# Potenta_connections.net
KiCad netlist of a schematic drawn in Altium Designer
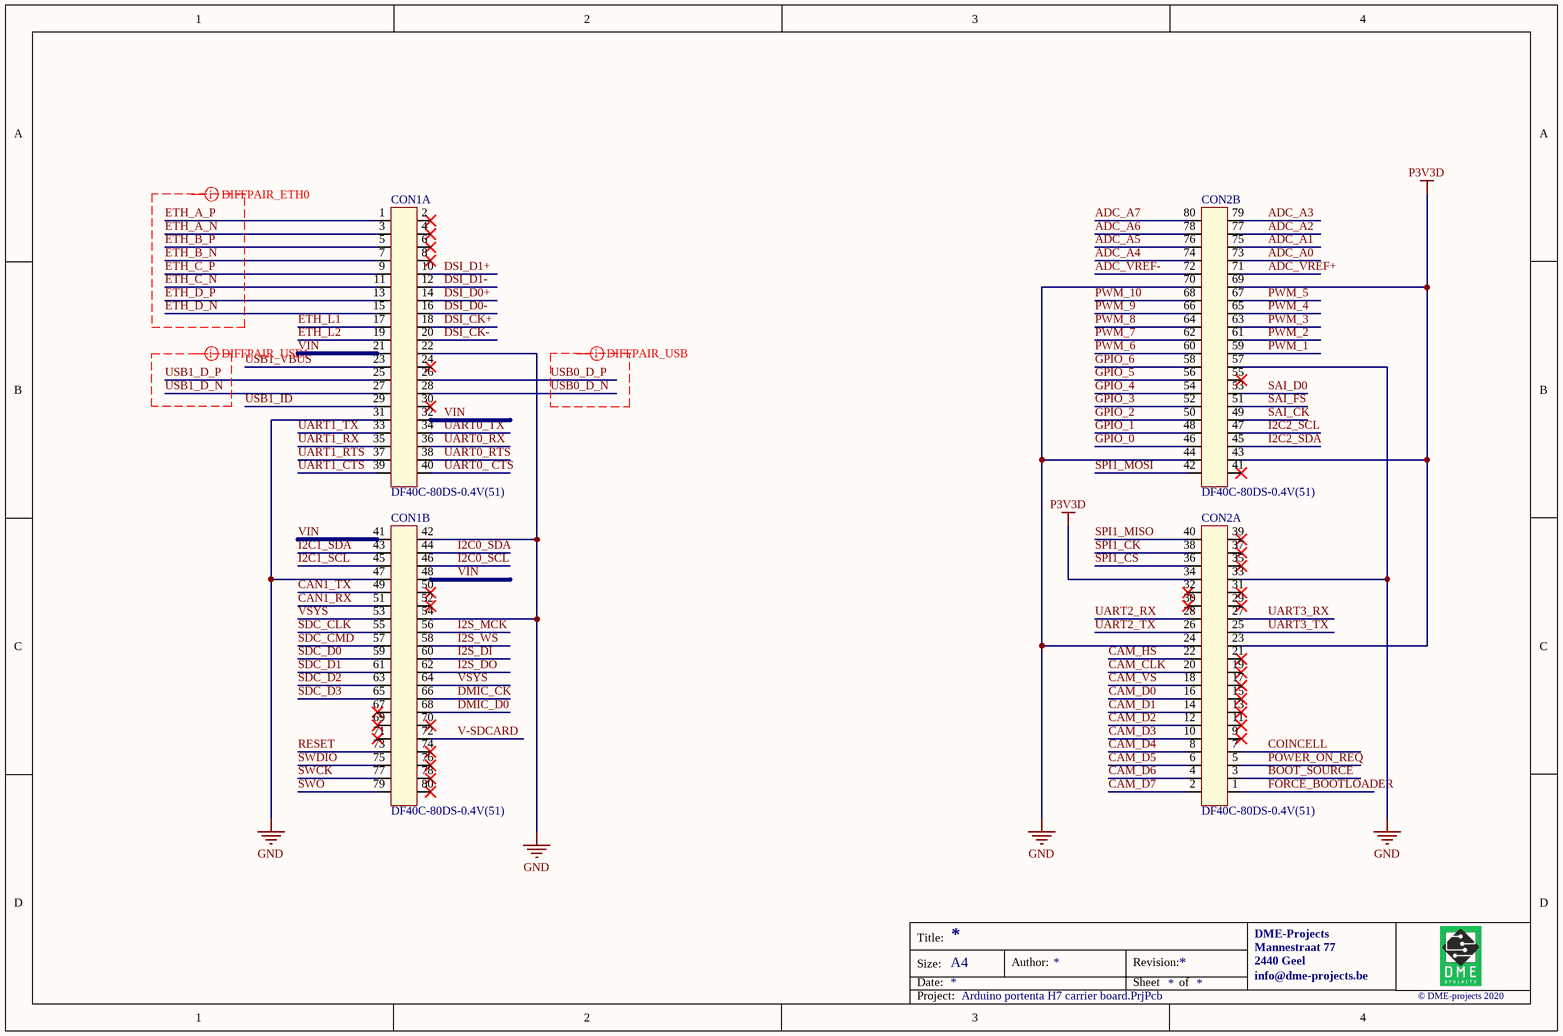
[diagram p0: Potenta connections.SchDoc]

(export (version "E")
  (design (tool "Eeschema 10.0.6"))
  (components
    (comp (ref "CON1")
      (value "DF40C-80DS-0.4V(51)")
      (footprint "DF40C-80DS-0.4V(51)-Footprint-1")
      (description "DF40 Series 80 Positions 0.4 mm Pitch Dual Row SMT Receptacle Connector")
      (libsource (lib "") (part "DF40C-80DS-0.4V(51)_1"))
    )
    (comp (ref "CON2")
      (value "DF40C-80DS-0.4V(51)")
      (footprint "DF40C-80DS-0.4V(51)-Footprint-1")
      (description "DF40 Series 80 Positions 0.4 mm Pitch Dual Row SMT Receptacle Connector")
      (libsource (lib "MIRION Technologies (CANBERRA Olen) NV") (part "DF40C-80DS-0.4V(51)"))
    )
  )
  (nets
    (net (code "1") (name "/ADC_A0") (class "Default")
      (node (ref "CON2") (pin "73") (pinfunction "73_73") (pintype "passive"))
    )
    (net (code "2") (name "/ADC_A1") (class "Default")
      (node (ref "CON2") (pin "75") (pinfunction "75_75") (pintype "passive"))
    )
    (net (code "3") (name "/ADC_A2") (class "Default")
      (node (ref "CON2") (pin "77") (pinfunction "77_77") (pintype "passive"))
    )
    (net (code "4") (name "/ADC_A3") (class "Default")
      (node (ref "CON2") (pin "79") (pinfunction "79_79") (pintype "passive"))
    )
    (net (code "5") (name "/ADC_A4") (class "Default")
      (node (ref "CON2") (pin "74") (pinfunction "74_74") (pintype "passive"))
    )
    (net (code "6") (name "/ADC_A5") (class "Default")
      (node (ref "CON2") (pin "76") (pinfunction "76_76") (pintype "passive"))
    )
    (net (code "7") (name "/ADC_A6") (class "Default")
      (node (ref "CON2") (pin "78") (pinfunction "78_78") (pintype "passive"))
    )
    (net (code "8") (name "/ADC_A7") (class "Default")
      (node (ref "CON2") (pin "80") (pinfunction "80_80") (pintype "passive"))
    )
    (net (code "9") (name "/ADC_VREF+") (class "Default")
      (node (ref "CON2") (pin "71") (pinfunction "71_71") (pintype "passive"))
    )
    (net (code "10") (name "/ADC_VREF-") (class "Default")
      (node (ref "CON2") (pin "72") (pinfunction "72_72") (pintype "passive"))
    )
    (net (code "11") (name "/BOOT_SOURCE") (class "Default")
      (node (ref "CON2") (pin "3") (pinfunction "3_3") (pintype "passive"))
    )
    (net (code "12") (name "/CAM_CLK") (class "Default")
      (node (ref "CON2") (pin "20") (pinfunction "20_20") (pintype "passive"))
    )
    (net (code "13") (name "/CAM_D0") (class "Default")
      (node (ref "CON2") (pin "16") (pinfunction "16_16") (pintype "passive"))
    )
    (net (code "14") (name "/CAM_D1") (class "Default")
      (node (ref "CON2") (pin "14") (pinfunction "14_14") (pintype "passive"))
    )
    (net (code "15") (name "/CAM_D2") (class "Default")
      (node (ref "CON2") (pin "12") (pinfunction "12_12") (pintype "passive"))
    )
    (net (code "16") (name "/CAM_D3") (class "Default")
      (node (ref "CON2") (pin "10") (pinfunction "10_10") (pintype "passive"))
    )
    (net (code "17") (name "/CAM_D4") (class "Default")
      (node (ref "CON2") (pin "8") (pinfunction "8_8") (pintype "passive"))
    )
    (net (code "18") (name "/CAM_D5") (class "Default")
      (node (ref "CON2") (pin "6") (pinfunction "6_6") (pintype "passive"))
    )
    (net (code "19") (name "/CAM_D6") (class "Default")
      (node (ref "CON2") (pin "4") (pinfunction "4_4") (pintype "passive"))
    )
    (net (code "20") (name "/CAM_D7") (class "Default")
      (node (ref "CON2") (pin "2") (pinfunction "2_2") (pintype "passive"))
    )
    (net (code "21") (name "/CAM_HS") (class "Default")
      (node (ref "CON2") (pin "22") (pinfunction "22_22") (pintype "passive"))
    )
    (net (code "22") (name "/CAM_VS") (class "Default")
      (node (ref "CON2") (pin "18") (pinfunction "18_18") (pintype "passive"))
    )
    (net (code "23") (name "/CAN1_RX") (class "Default")
      (node (ref "CON1") (pin "51") (pinfunction "51_51") (pintype "passive"))
    )
    (net (code "24") (name "/CAN1_TX") (class "Default")
      (node (ref "CON1") (pin "49") (pinfunction "49_49") (pintype "passive"))
    )
    (net (code "25") (name "/COINCELL") (class "Default")
      (node (ref "CON2") (pin "7") (pinfunction "7_7") (pintype "passive"))
    )
    (net (code "26") (name "/DMIC_CK") (class "Default")
      (node (ref "CON1") (pin "66") (pinfunction "66_66") (pintype "passive"))
    )
    (net (code "27") (name "/DMIC_D0") (class "Default")
      (node (ref "CON1") (pin "68") (pinfunction "68_68") (pintype "passive"))
    )
    (net (code "28") (name "/DSI_CK+") (class "Default")
      (node (ref "CON1") (pin "18") (pinfunction "18_18") (pintype "passive"))
    )
    (net (code "29") (name "/DSI_CK-") (class "Default")
      (node (ref "CON1") (pin "20") (pinfunction "20_20") (pintype "passive"))
    )
    (net (code "30") (name "/DSI_D0+") (class "Default")
      (node (ref "CON1") (pin "14") (pinfunction "14_14") (pintype "passive"))
    )
    (net (code "31") (name "/DSI_D0-") (class "Default")
      (node (ref "CON1") (pin "16") (pinfunction "16_16") (pintype "passive"))
    )
    (net (code "32") (name "/DSI_D1+") (class "Default")
      (node (ref "CON1") (pin "10") (pinfunction "10_10") (pintype "passive"))
    )
    (net (code "33") (name "/DSI_D1-") (class "Default")
      (node (ref "CON1") (pin "12") (pinfunction "12_12") (pintype "passive"))
    )
    (net (code "34") (name "/ETH_A_N") (class "Default")
      (node (ref "CON1") (pin "3") (pinfunction "3_3") (pintype "passive"))
    )
    (net (code "35") (name "/ETH_A_P") (class "Default")
      (node (ref "CON1") (pin "1") (pinfunction "1_1") (pintype "passive"))
    )
    (net (code "36") (name "/ETH_B_N") (class "Default")
      (node (ref "CON1") (pin "7") (pinfunction "7_7") (pintype "passive"))
    )
    (net (code "37") (name "/ETH_B_P") (class "Default")
      (node (ref "CON1") (pin "5") (pinfunction "5_5") (pintype "passive"))
    )
    (net (code "38") (name "/ETH_C_N") (class "Default")
      (node (ref "CON1") (pin "11") (pinfunction "11_11") (pintype "passive"))
    )
    (net (code "39") (name "/ETH_C_P") (class "Default")
      (node (ref "CON1") (pin "9") (pinfunction "9_9") (pintype "passive"))
    )
    (net (code "40") (name "/ETH_D_N") (class "Default")
      (node (ref "CON1") (pin "15") (pinfunction "15_15") (pintype "passive"))
    )
    (net (code "41") (name "/ETH_D_P") (class "Default")
      (node (ref "CON1") (pin "13") (pinfunction "13_13") (pintype "passive"))
    )
    (net (code "42") (name "/ETH_L1") (class "Default")
      (node (ref "CON1") (pin "17") (pinfunction "17_17") (pintype "passive"))
    )
    (net (code "43") (name "/ETH_L2") (class "Default")
      (node (ref "CON1") (pin "19") (pinfunction "19_19") (pintype "passive"))
    )
    (net (code "44") (name "/FORCE_BOOTLOADER") (class "Default")
      (node (ref "CON2") (pin "1") (pinfunction "1_1") (pintype "passive"))
    )
    (net (code "45") (name "/GPIO_0") (class "Default")
      (node (ref "CON2") (pin "46") (pinfunction "46_46") (pintype "passive"))
    )
    (net (code "46") (name "/GPIO_1") (class "Default")
      (node (ref "CON2") (pin "48") (pinfunction "48_48") (pintype "passive"))
    )
    (net (code "47") (name "/GPIO_2") (class "Default")
      (node (ref "CON2") (pin "50") (pinfunction "50_50") (pintype "passive"))
    )
    (net (code "48") (name "/GPIO_3") (class "Default")
      (node (ref "CON2") (pin "52") (pinfunction "52_52") (pintype "passive"))
    )
    (net (code "49") (name "/GPIO_4") (class "Default")
      (node (ref "CON2") (pin "54") (pinfunction "54_54") (pintype "passive"))
    )
    (net (code "50") (name "/GPIO_5") (class "Default")
      (node (ref "CON2") (pin "56") (pinfunction "56_56") (pintype "passive"))
    )
    (net (code "51") (name "/GPIO_6") (class "Default")
      (node (ref "CON2") (pin "58") (pinfunction "58_58") (pintype "passive"))
    )
    (net (code "52") (name "/I2C0_SCL") (class "Default")
      (node (ref "CON1") (pin "46") (pinfunction "46_46") (pintype "passive"))
    )
    (net (code "53") (name "/I2C0_SDA") (class "Default")
      (node (ref "CON1") (pin "44") (pinfunction "44_44") (pintype "passive"))
    )
    (net (code "54") (name "/I2C1_SCL") (class "Default")
      (node (ref "CON1") (pin "45") (pinfunction "45_45") (pintype "passive"))
    )
    (net (code "55") (name "/I2C1_SDA") (class "Default")
      (node (ref "CON1") (pin "43") (pinfunction "43_43") (pintype "passive"))
    )
    (net (code "56") (name "/I2C2_SCL") (class "Default")
      (node (ref "CON2") (pin "47") (pinfunction "47_47") (pintype "passive"))
    )
    (net (code "57") (name "/I2C2_SDA") (class "Default")
      (node (ref "CON2") (pin "45") (pinfunction "45_45") (pintype "passive"))
    )
    (net (code "58") (name "/I2S_DI") (class "Default")
      (node (ref "CON1") (pin "60") (pinfunction "60_60") (pintype "passive"))
    )
    (net (code "59") (name "/I2S_DO") (class "Default")
      (node (ref "CON1") (pin "62") (pinfunction "62_62") (pintype "passive"))
    )
    (net (code "60") (name "/I2S_MCK") (class "Default")
      (node (ref "CON1") (pin "56") (pinfunction "56_56") (pintype "passive"))
    )
    (net (code "61") (name "/I2S_WS") (class "Default")
      (node (ref "CON1") (pin "58") (pinfunction "58_58") (pintype "passive"))
    )
    (net (code "62") (name "/POWER_ON_REQ") (class "Default")
      (node (ref "CON2") (pin "5") (pinfunction "5_5") (pintype "passive"))
    )
    (net (code "63") (name "/PWM_1") (class "Default")
      (node (ref "CON2") (pin "59") (pinfunction "59_59") (pintype "passive"))
    )
    (net (code "64") (name "/PWM_2") (class "Default")
      (node (ref "CON2") (pin "61") (pinfunction "61_61") (pintype "passive"))
    )
    (net (code "65") (name "/PWM_3") (class "Default")
      (node (ref "CON2") (pin "63") (pinfunction "63_63") (pintype "passive"))
    )
    (net (code "66") (name "/PWM_4") (class "Default")
      (node (ref "CON2") (pin "65") (pinfunction "65_65") (pintype "passive"))
    )
    (net (code "67") (name "/PWM_5") (class "Default")
      (node (ref "CON2") (pin "67") (pinfunction "67_67") (pintype "passive"))
    )
    (net (code "68") (name "/PWM_6") (class "Default")
      (node (ref "CON2") (pin "60") (pinfunction "60_60") (pintype "passive"))
    )
    (net (code "69") (name "/PWM_7") (class "Default")
      (node (ref "CON2") (pin "62") (pinfunction "62_62") (pintype "passive"))
    )
    (net (code "70") (name "/PWM_8") (class "Default")
      (node (ref "CON2") (pin "64") (pinfunction "64_64") (pintype "passive"))
    )
    (net (code "71") (name "/PWM_9") (class "Default")
      (node (ref "CON2") (pin "66") (pinfunction "66_66") (pintype "passive"))
    )
    (net (code "72") (name "/PWM_10") (class "Default")
      (node (ref "CON2") (pin "68") (pinfunction "68_68") (pintype "passive"))
    )
    (net (code "73") (name "/RESET") (class "Default")
      (node (ref "CON1") (pin "73") (pinfunction "73_73") (pintype "passive"))
    )
    (net (code "74") (name "/SAI_CK") (class "Default")
      (node (ref "CON2") (pin "49") (pinfunction "49_49") (pintype "passive"))
    )
    (net (code "75") (name "/SAI_D0") (class "Default")
      (node (ref "CON2") (pin "53") (pinfunction "53_53") (pintype "passive"))
    )
    (net (code "76") (name "/SAI_FS") (class "Default")
      (node (ref "CON2") (pin "51") (pinfunction "51_51") (pintype "passive"))
    )
    (net (code "77") (name "/SDC_CLK") (class "Default")
      (node (ref "CON1") (pin "55") (pinfunction "55_55") (pintype "passive"))
    )
    (net (code "78") (name "/SDC_CMD") (class "Default")
      (node (ref "CON1") (pin "57") (pinfunction "57_57") (pintype "passive"))
    )
    (net (code "79") (name "/SDC_D0") (class "Default")
      (node (ref "CON1") (pin "59") (pinfunction "59_59") (pintype "passive"))
    )
    (net (code "80") (name "/SDC_D1") (class "Default")
      (node (ref "CON1") (pin "61") (pinfunction "61_61") (pintype "passive"))
    )
    (net (code "81") (name "/SDC_D2") (class "Default")
      (node (ref "CON1") (pin "63") (pinfunction "63_63") (pintype "passive"))
    )
    (net (code "82") (name "/SDC_D3") (class "Default")
      (node (ref "CON1") (pin "65") (pinfunction "65_65") (pintype "passive"))
    )
    (net (code "83") (name "/SPI1_CK") (class "Default")
      (node (ref "CON2") (pin "38") (pinfunction "38_38") (pintype "passive"))
    )
    (net (code "84") (name "/SPI1_CS") (class "Default")
      (node (ref "CON2") (pin "36") (pinfunction "36_36") (pintype "passive"))
    )
    (net (code "85") (name "/SPI1_MISO") (class "Default")
      (node (ref "CON2") (pin "40") (pinfunction "40_40") (pintype "passive"))
    )
    (net (code "86") (name "/SPI1_MOSI") (class "Default")
      (node (ref "CON2") (pin "42") (pinfunction "42_42") (pintype "passive"))
    )
    (net (code "87") (name "/SWCK") (class "Default")
      (node (ref "CON1") (pin "77") (pinfunction "77_77") (pintype "passive"))
    )
    (net (code "88") (name "/SWDIO") (class "Default")
      (node (ref "CON1") (pin "75") (pinfunction "75_75") (pintype "passive"))
    )
    (net (code "89") (name "/SWO") (class "Default")
      (node (ref "CON1") (pin "79") (pinfunction "79_79") (pintype "passive"))
    )
    (net (code "90") (name "/UART0_ CTS") (class "Default")
      (node (ref "CON1") (pin "40") (pinfunction "40_40") (pintype "passive"))
    )
    (net (code "91") (name "/UART0_RTS") (class "Default")
      (node (ref "CON1") (pin "38") (pinfunction "38_38") (pintype "passive"))
    )
    (net (code "92") (name "/UART0_RX") (class "Default")
      (node (ref "CON1") (pin "36") (pinfunction "36_36") (pintype "passive"))
    )
    (net (code "93") (name "/UART0_TX") (class "Default")
      (node (ref "CON1") (pin "34") (pinfunction "34_34") (pintype "passive"))
    )
    (net (code "94") (name "/UART1_CTS") (class "Default")
      (node (ref "CON1") (pin "39") (pinfunction "39_39") (pintype "passive"))
    )
    (net (code "95") (name "/UART1_RTS") (class "Default")
      (node (ref "CON1") (pin "37") (pinfunction "37_37") (pintype "passive"))
    )
    (net (code "96") (name "/UART1_RX") (class "Default")
      (node (ref "CON1") (pin "35") (pinfunction "35_35") (pintype "passive"))
    )
    (net (code "97") (name "/UART1_TX") (class "Default")
      (node (ref "CON1") (pin "33") (pinfunction "33_33") (pintype "passive"))
    )
    (net (code "98") (name "/UART2_RX") (class "Default")
      (node (ref "CON2") (pin "28") (pinfunction "28_28") (pintype "passive"))
    )
    (net (code "99") (name "/UART2_TX") (class "Default")
      (node (ref "CON2") (pin "26") (pinfunction "26_26") (pintype "passive"))
    )
    (net (code "100") (name "/UART3_RX") (class "Default")
      (node (ref "CON2") (pin "27") (pinfunction "27_27") (pintype "passive"))
    )
    (net (code "101") (name "/UART3_TX") (class "Default")
      (node (ref "CON2") (pin "25") (pinfunction "25_25") (pintype "passive"))
    )
    (net (code "102") (name "/USB0_D_N") (class "Default")
      (node (ref "CON1") (pin "28") (pinfunction "28_28") (pintype "passive"))
    )
    (net (code "103") (name "/USB0_D_P") (class "Default")
      (node (ref "CON1") (pin "26") (pinfunction "26_26") (pintype "passive"))
    )
    (net (code "104") (name "/USB1_D_N") (class "Default")
      (node (ref "CON1") (pin "27") (pinfunction "27_27") (pintype "passive"))
    )
    (net (code "105") (name "/USB1_D_P") (class "Default")
      (node (ref "CON1") (pin "25") (pinfunction "25_25") (pintype "passive"))
    )
    (net (code "106") (name "/USB1_ID") (class "Default")
      (node (ref "CON1") (pin "29") (pinfunction "29_29") (pintype "passive"))
    )
    (net (code "107") (name "/USB1_VBUS") (class "Default")
      (node (ref "CON1") (pin "23") (pinfunction "23_23") (pintype "passive"))
    )
    (net (code "108") (name "/V-SDCARD") (class "Default")
      (node (ref "CON1") (pin "72") (pinfunction "72_72") (pintype "passive"))
    )
    (net (code "109") (name "/VIN") (class "Default")
      (node (ref "CON1") (pin "21") (pinfunction "21_21") (pintype "passive"))
      (node (ref "CON1") (pin "32") (pinfunction "32_32") (pintype "passive"))
      (node (ref "CON1") (pin "41") (pinfunction "41_41") (pintype "passive"))
      (node (ref "CON1") (pin "48") (pinfunction "48_48") (pintype "passive"))
    )
    (net (code "110") (name "/VSYS") (class "Default")
      (node (ref "CON1") (pin "53") (pinfunction "53_53") (pintype "passive"))
      (node (ref "CON1") (pin "64") (pinfunction "64_64") (pintype "passive"))
    )
    (net (code "111") (name "GND") (class "Default")
      (node (ref "CON1") (pin "22") (pinfunction "22_22") (pintype "passive"))
      (node (ref "CON1") (pin "31") (pinfunction "31_31") (pintype "passive"))
      (node (ref "CON1") (pin "42") (pinfunction "42_42") (pintype "passive"))
      (node (ref "CON1") (pin "47") (pinfunction "47_47") (pintype "passive"))
      (node (ref "CON1") (pin "54") (pinfunction "54_54") (pintype "passive"))
      (node (ref "CON2") (pin "24") (pinfunction "24_24") (pintype "passive"))
      (node (ref "CON2") (pin "33") (pinfunction "33_33") (pintype "passive"))
      (node (ref "CON2") (pin "44") (pinfunction "44_44") (pintype "passive"))
      (node (ref "CON2") (pin "57") (pinfunction "57_57") (pintype "passive"))
      (node (ref "CON2") (pin "70") (pinfunction "70_70") (pintype "passive"))
    )
    (net (code "112") (name "P3V3D") (class "Default")
      (node (ref "CON2") (pin "23") (pinfunction "23_23") (pintype "passive"))
      (node (ref "CON2") (pin "34") (pinfunction "34_34") (pintype "passive"))
      (node (ref "CON2") (pin "43") (pinfunction "43_43") (pintype "passive"))
      (node (ref "CON2") (pin "69") (pinfunction "69_69") (pintype "passive"))
    )
    (net (code "113") (name "unconnected-(CON1-Pad2)") (class "Default")
      (node (ref "CON1") (pin "2") (pinfunction "2_2") (pintype "passive+no_connect"))
    )
    (net (code "114") (name "unconnected-(CON1-Pad4)") (class "Default")
      (node (ref "CON1") (pin "4") (pinfunction "4_4") (pintype "passive+no_connect"))
    )
    (net (code "115") (name "unconnected-(CON1-Pad6)") (class "Default")
      (node (ref "CON1") (pin "6") (pinfunction "6_6") (pintype "passive+no_connect"))
    )
    (net (code "116") (name "unconnected-(CON1-Pad8)") (class "Default")
      (node (ref "CON1") (pin "8") (pinfunction "8_8") (pintype "passive+no_connect"))
    )
    (net (code "117") (name "unconnected-(CON1-Pad24)") (class "Default")
      (node (ref "CON1") (pin "24") (pinfunction "24_24") (pintype "passive+no_connect"))
    )
    (net (code "118") (name "unconnected-(CON1-Pad30)") (class "Default")
      (node (ref "CON1") (pin "30") (pinfunction "30_30") (pintype "passive+no_connect"))
    )
    (net (code "119") (name "unconnected-(CON1-Pad50)") (class "Default")
      (node (ref "CON1") (pin "50") (pinfunction "50_50") (pintype "passive+no_connect"))
    )
    (net (code "120") (name "unconnected-(CON1-Pad52)") (class "Default")
      (node (ref "CON1") (pin "52") (pinfunction "52_52") (pintype "passive+no_connect"))
    )
    (net (code "121") (name "unconnected-(CON1-Pad67)") (class "Default")
      (node (ref "CON1") (pin "67") (pinfunction "67_67") (pintype "passive+no_connect"))
    )
    (net (code "122") (name "unconnected-(CON1-Pad69)") (class "Default")
      (node (ref "CON1") (pin "69") (pinfunction "69_69") (pintype "passive+no_connect"))
    )
    (net (code "123") (name "unconnected-(CON1-Pad70)") (class "Default")
      (node (ref "CON1") (pin "70") (pinfunction "70_70") (pintype "passive+no_connect"))
    )
    (net (code "124") (name "unconnected-(CON1-Pad71)") (class "Default")
      (node (ref "CON1") (pin "71") (pinfunction "71_71") (pintype "passive+no_connect"))
    )
    (net (code "125") (name "unconnected-(CON1-Pad74)") (class "Default")
      (node (ref "CON1") (pin "74") (pinfunction "74_74") (pintype "passive+no_connect"))
    )
    (net (code "126") (name "unconnected-(CON1-Pad76)") (class "Default")
      (node (ref "CON1") (pin "76") (pinfunction "76_76") (pintype "passive+no_connect"))
    )
    (net (code "127") (name "unconnected-(CON1-Pad78)") (class "Default")
      (node (ref "CON1") (pin "78") (pinfunction "78_78") (pintype "passive+no_connect"))
    )
    (net (code "128") (name "unconnected-(CON1-Pad80)") (class "Default")
      (node (ref "CON1") (pin "80") (pinfunction "80_80") (pintype "passive+no_connect"))
    )
    (net (code "129") (name "unconnected-(CON2-Pad9)") (class "Default")
      (node (ref "CON2") (pin "9") (pinfunction "9_9") (pintype "passive+no_connect"))
    )
    (net (code "130") (name "unconnected-(CON2-Pad11)") (class "Default")
      (node (ref "CON2") (pin "11") (pinfunction "11_11") (pintype "passive+no_connect"))
    )
    (net (code "131") (name "unconnected-(CON2-Pad13)") (class "Default")
      (node (ref "CON2") (pin "13") (pinfunction "13_13") (pintype "passive+no_connect"))
    )
    (net (code "132") (name "unconnected-(CON2-Pad15)") (class "Default")
      (node (ref "CON2") (pin "15") (pinfunction "15_15") (pintype "passive+no_connect"))
    )
    (net (code "133") (name "unconnected-(CON2-Pad17)") (class "Default")
      (node (ref "CON2") (pin "17") (pinfunction "17_17") (pintype "passive+no_connect"))
    )
    (net (code "134") (name "unconnected-(CON2-Pad19)") (class "Default")
      (node (ref "CON2") (pin "19") (pinfunction "19_19") (pintype "passive+no_connect"))
    )
    (net (code "135") (name "unconnected-(CON2-Pad21)") (class "Default")
      (node (ref "CON2") (pin "21") (pinfunction "21_21") (pintype "passive+no_connect"))
    )
    (net (code "136") (name "unconnected-(CON2-Pad29)") (class "Default")
      (node (ref "CON2") (pin "29") (pinfunction "29_29") (pintype "passive+no_connect"))
    )
    (net (code "137") (name "unconnected-(CON2-Pad30)") (class "Default")
      (node (ref "CON2") (pin "30") (pinfunction "30_30") (pintype "passive+no_connect"))
    )
    (net (code "138") (name "unconnected-(CON2-Pad31)") (class "Default")
      (node (ref "CON2") (pin "31") (pinfunction "31_31") (pintype "passive+no_connect"))
    )
    (net (code "139") (name "unconnected-(CON2-Pad32)") (class "Default")
      (node (ref "CON2") (pin "32") (pinfunction "32_32") (pintype "passive+no_connect"))
    )
    (net (code "140") (name "unconnected-(CON2-Pad35)") (class "Default")
      (node (ref "CON2") (pin "35") (pinfunction "35_35") (pintype "passive+no_connect"))
    )
    (net (code "141") (name "unconnected-(CON2-Pad37)") (class "Default")
      (node (ref "CON2") (pin "37") (pinfunction "37_37") (pintype "passive+no_connect"))
    )
    (net (code "142") (name "unconnected-(CON2-Pad39)") (class "Default")
      (node (ref "CON2") (pin "39") (pinfunction "39_39") (pintype "passive+no_connect"))
    )
    (net (code "143") (name "unconnected-(CON2-Pad41)") (class "Default")
      (node (ref "CON2") (pin "41") (pinfunction "41_41") (pintype "passive+no_connect"))
    )
    (net (code "144") (name "unconnected-(CON2-Pad55)") (class "Default")
      (node (ref "CON2") (pin "55") (pinfunction "55_55") (pintype "passive+no_connect"))
    )
  )
)
